# PIZ-Dual_v886.net
KiCad netlist of a schematic drawn in EAGLE
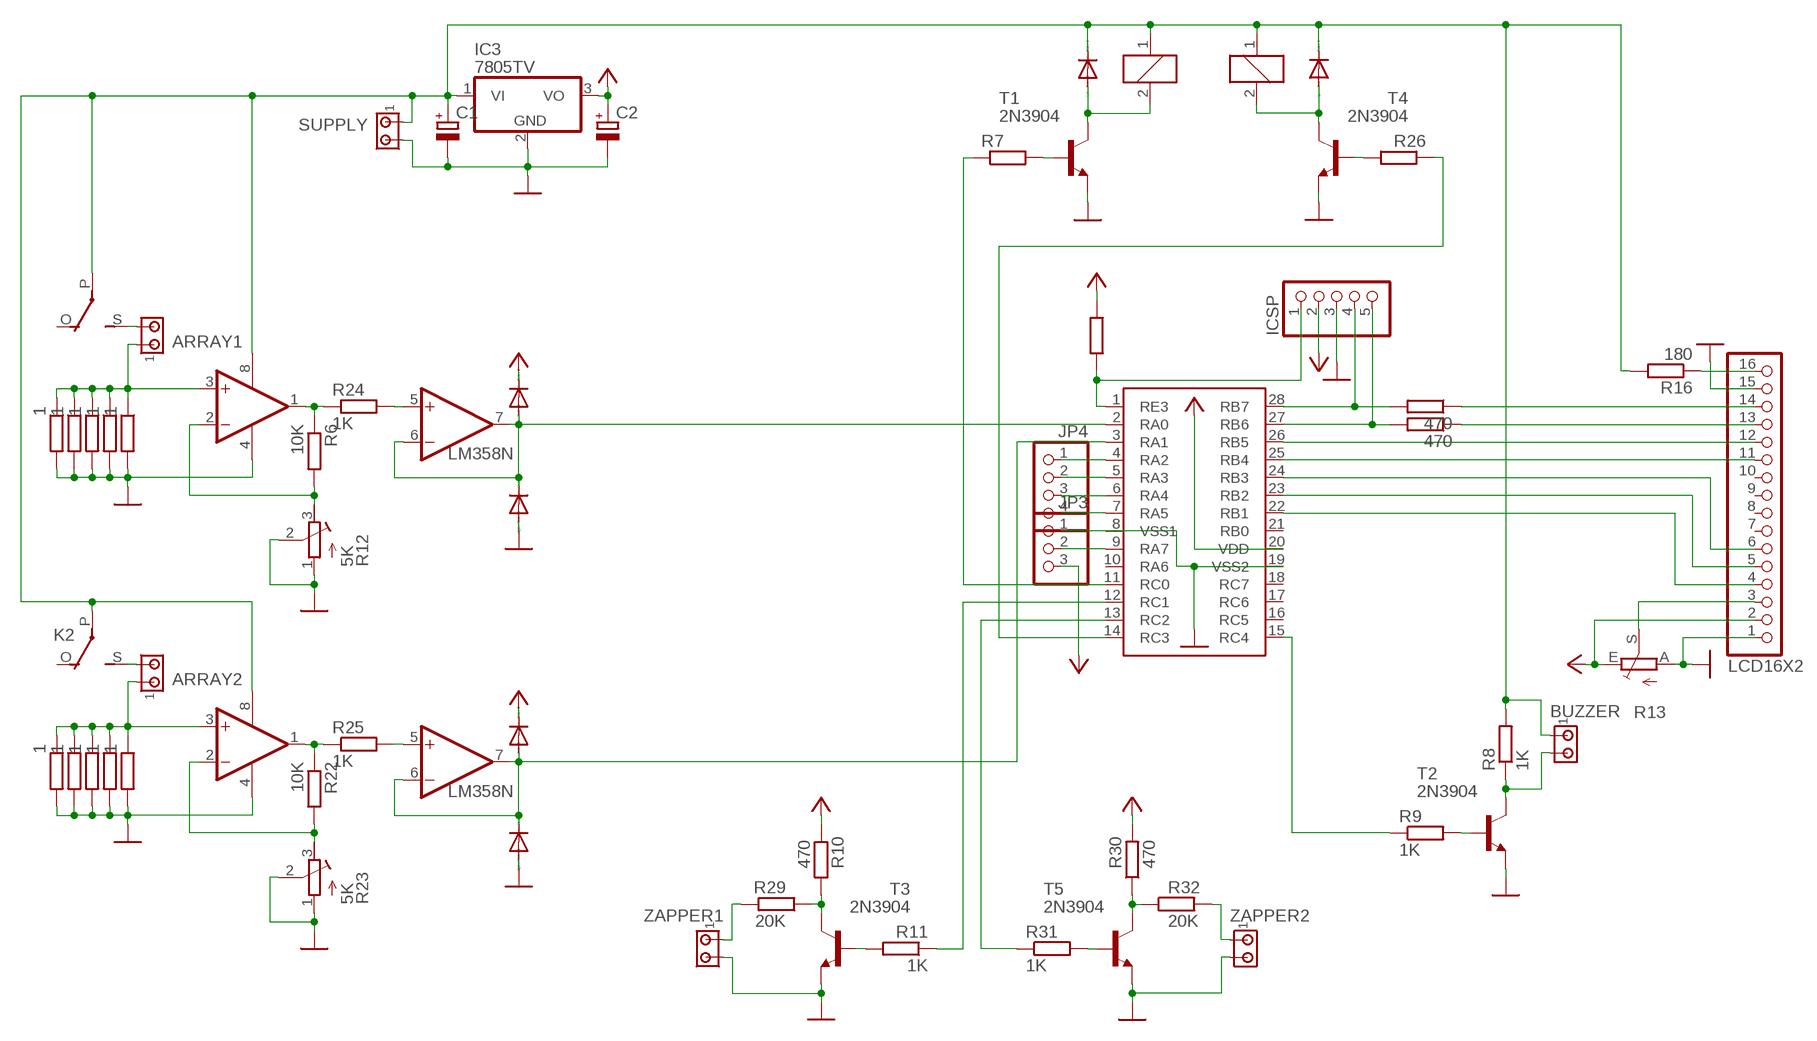
[diagram p0: schematic, sheet 1]

(export (version "E")
  (design (tool "Eeschema 10.0.6"))
  (components
    (comp (ref "ARRAY1")
      (value "MTA02-100")
      (footprint "eagle-import:10X02MTA")
      (libsource (lib "eagle-import") (part "MTA02-100"))
    )
    (comp (ref "ARRAY2")
      (value "MTA02-100")
      (footprint "eagle-import:10X02MTA")
      (libsource (lib "eagle-import") (part "MTA02-100"))
    )
    (comp (ref "BUZZER")
      (value "MTA02-100")
      (footprint "eagle-import:10X02MTA")
      (libsource (lib "eagle-import") (part "MTA02-100"))
    )
    (comp (ref "C1")
      (value "CPOL-EUE2.5-7")
      (footprint "eagle-import:E2,5-7")
      (libsource (lib "eagle-import") (part "CPOL-EUE2.5-7"))
    )
    (comp (ref "C2")
      (value "CPOL-EUE2.5-7")
      (footprint "eagle-import:E2,5-7")
      (libsource (lib "eagle-import") (part "CPOL-EUE2.5-7"))
    )
    (comp (ref "D1")
      (value "1N4148DO35-7")
      (footprint "eagle-import:DO35-7")
      (libsource (lib "eagle-import") (part "1N4148DO35-7"))
    )
    (comp (ref "D2")
      (value "1N4148DO35-7")
      (footprint "eagle-import:DO35-7")
      (libsource (lib "eagle-import") (part "1N4148DO35-7"))
    )
    (comp (ref "D3")
      (value "1N4148DO35-7")
      (footprint "eagle-import:DO35-7")
      (libsource (lib "eagle-import") (part "1N4148DO35-7"))
    )
    (comp (ref "D4")
      (value "1N4148DO35-7")
      (footprint "eagle-import:DO35-7")
      (libsource (lib "eagle-import") (part "1N4148DO35-7"))
    )
    (comp (ref "D5")
      (value "1N4148DO35-7")
      (footprint "eagle-import:DO35-7")
      (libsource (lib "eagle-import") (part "1N4148DO35-7"))
    )
    (comp (ref "D6")
      (value "1N4148DO35-7")
      (footprint "eagle-import:DO35-7")
      (libsource (lib "eagle-import") (part "1N4148DO35-7"))
    )
    (comp (ref "IC2")
      (value "LM358N")
      (footprint "eagle-import:DIL08")
      (libsource (lib "eagle-import") (part "LM358N"))
    )
    (comp (ref "IC3")
      (value "7805TV")
      (footprint "eagle-import:TO220V")
      (libsource (lib "eagle-import") (part "78TV05"))
    )
    (comp (ref "IC4")
      (value "LM358N")
      (footprint "eagle-import:DIL08")
      (libsource (lib "eagle-import") (part "LM358N"))
    )
    (comp (ref "ICSP")
      (value "PINHD-1X55X2MM")
      (footprint "eagle-import:1_05X2MM")
      (libsource (lib "eagle-import") (part "PINHD-1X55X2MM"))
    )
    (comp (ref "JP3")
      (value "PINHD-1X3")
      (footprint "eagle-import:1X03")
      (libsource (lib "eagle-import") (part "PINHD-1X3"))
    )
    (comp (ref "JP4")
      (value "PINHD-1X4")
      (footprint "eagle-import:1X04")
      (libsource (lib "eagle-import") (part "PINHD-1X4"))
    )
    (comp (ref "K1")
      (value "G5L")
      (footprint "eagle-import:G5LE")
      (libsource (lib "eagle-import") (part "G5L"))
    )
    (comp (ref "K2")
      (value "G5L")
      (footprint "eagle-import:G5LE")
      (libsource (lib "eagle-import") (part "G5L"))
    )
    (comp (ref "LCD16X2")
      (value "PINHD-1X16")
      (footprint "eagle-import:1X16")
      (libsource (lib "eagle-import") (part "PINHD-1X16"))
    )
    (comp (ref "R1")
      (value "1")
      (footprint "eagle-import:0204_7")
      (libsource (lib "eagle-import") (part "R-EU_0204/7"))
    )
    (comp (ref "R2")
      (value "1")
      (footprint "eagle-import:0204_7")
      (libsource (lib "eagle-import") (part "R-EU_0204/7"))
    )
    (comp (ref "R3")
      (value "1")
      (footprint "eagle-import:0204_7")
      (libsource (lib "eagle-import") (part "R-EU_0204/7"))
    )
    (comp (ref "R4")
      (value "1")
      (footprint "eagle-import:0204_7")
      (libsource (lib "eagle-import") (part "R-EU_0204/7"))
    )
    (comp (ref "R5")
      (value "1")
      (footprint "eagle-import:0204_7")
      (libsource (lib "eagle-import") (part "R-EU_0204/7"))
    )
    (comp (ref "R6")
      (value "10K")
      (footprint "eagle-import:0204_7")
      (libsource (lib "eagle-import") (part "R-EU_0204/7"))
    )
    (comp (ref "R7")
      (value "R-EU_0204/7")
      (footprint "eagle-import:0204_7")
      (libsource (lib "eagle-import") (part "R-EU_0204/7"))
    )
    (comp (ref "R8")
      (value "1K")
      (footprint "eagle-import:0204_7")
      (libsource (lib "eagle-import") (part "R-EU_0204/7"))
    )
    (comp (ref "R9")
      (value "1K")
      (footprint "eagle-import:0204_7")
      (libsource (lib "eagle-import") (part "R-EU_0204/7"))
    )
    (comp (ref "R10")
      (value "470")
      (footprint "eagle-import:0204_7")
      (libsource (lib "eagle-import") (part "R-EU_0204/7"))
    )
    (comp (ref "R11")
      (value "1K")
      (footprint "eagle-import:0204_7")
      (libsource (lib "eagle-import") (part "R-EU_0204/7"))
    )
    (comp (ref "R12")
      (value "5K")
      (footprint "eagle-import:RTRIM64W")
      (libsource (lib "eagle-import") (part "R-TRIMM64W"))
    )
    (comp (ref "R13")
      (value "TRIM_EU-CA6V")
      (footprint "eagle-import:CA6V")
      (libsource (lib "eagle-import") (part "TRIM_EU-CA6V"))
    )
    (comp (ref "R16")
      (value "180")
      (footprint "eagle-import:0309_10")
      (libsource (lib "eagle-import") (part "R-EU_0309/10"))
    )
    (comp (ref "R17")
      (value "1")
      (footprint "eagle-import:0204_7")
      (libsource (lib "eagle-import") (part "R-EU_0204/7"))
    )
    (comp (ref "R18")
      (value "1")
      (footprint "eagle-import:0204_7")
      (libsource (lib "eagle-import") (part "R-EU_0204/7"))
    )
    (comp (ref "R19")
      (value "1")
      (footprint "eagle-import:0204_7")
      (libsource (lib "eagle-import") (part "R-EU_0204/7"))
    )
    (comp (ref "R20")
      (value "1")
      (footprint "eagle-import:0204_7")
      (libsource (lib "eagle-import") (part "R-EU_0204/7"))
    )
    (comp (ref "R21")
      (value "1")
      (footprint "eagle-import:0204_7")
      (libsource (lib "eagle-import") (part "R-EU_0204/7"))
    )
    (comp (ref "R22")
      (value "10K")
      (footprint "eagle-import:0204_7")
      (libsource (lib "eagle-import") (part "R-EU_0204/7"))
    )
    (comp (ref "R23")
      (value "5K")
      (footprint "eagle-import:RTRIM64W")
      (libsource (lib "eagle-import") (part "R-TRIMM64W"))
    )
    (comp (ref "R24")
      (value "1K")
      (footprint "eagle-import:0204_7")
      (libsource (lib "eagle-import") (part "R-EU_0204/7"))
    )
    (comp (ref "R25")
      (value "1K")
      (footprint "eagle-import:0204_7")
      (libsource (lib "eagle-import") (part "R-EU_0204/7"))
    )
    (comp (ref "R26")
      (value "R-EU_0204/7")
      (footprint "eagle-import:0204_7")
      (libsource (lib "eagle-import") (part "R-EU_0204/7"))
    )
    (comp (ref "R27")
      (value "470")
      (footprint "eagle-import:0204_7")
      (libsource (lib "eagle-import") (part "R-EU_0204/7"))
    )
    (comp (ref "R28")
      (value "470")
      (footprint "eagle-import:0204_7")
      (libsource (lib "eagle-import") (part "R-EU_0204/7"))
    )
    (comp (ref "R29")
      (value "20K")
      (footprint "eagle-import:0204_7")
      (libsource (lib "eagle-import") (part "R-EU_0204/7"))
    )
    (comp (ref "R30")
      (value "470")
      (footprint "eagle-import:0204_7")
      (libsource (lib "eagle-import") (part "R-EU_0204/7"))
    )
    (comp (ref "R31")
      (value "1K")
      (footprint "eagle-import:0204_7")
      (libsource (lib "eagle-import") (part "R-EU_0204/7"))
    )
    (comp (ref "R32")
      (value "20K")
      (footprint "eagle-import:0204_7")
      (libsource (lib "eagle-import") (part "R-EU_0204/7"))
    )
    (comp (ref "R33")
      (value "10K")
      (footprint "eagle-import:0204_7")
      (libsource (lib "eagle-import") (part "R-EU_0204/7"))
    )
    (comp (ref "SUPPLY")
      (value "MTA02-100")
      (footprint "eagle-import:10X02MTA")
      (libsource (lib "eagle-import") (part "MTA02-100"))
    )
    (comp (ref "T1")
      (value "2N3904")
      (footprint "eagle-import:TO92")
      (libsource (lib "eagle-import") (part "2N3904"))
    )
    (comp (ref "T2")
      (value "2N3904")
      (footprint "eagle-import:TO92")
      (libsource (lib "eagle-import") (part "2N3904"))
    )
    (comp (ref "T3")
      (value "2N3904")
      (footprint "eagle-import:TO92")
      (libsource (lib "eagle-import") (part "2N3904"))
    )
    (comp (ref "T4")
      (value "2N3904")
      (footprint "eagle-import:TO92")
      (libsource (lib "eagle-import") (part "2N3904"))
    )
    (comp (ref "T5")
      (value "2N3904")
      (footprint "eagle-import:TO92")
      (libsource (lib "eagle-import") (part "2N3904"))
    )
    (comp (ref "U$1")
      (value "PIC16F88")
      (footprint "eagle-import:SO28W")
      (libsource (lib "eagle-import") (part "PIC16F88"))
    )
    (comp (ref "ZAPPER1")
      (value "MTA02-100")
      (footprint "eagle-import:10X02MTA")
      (libsource (lib "eagle-import") (part "MTA02-100"))
    )
    (comp (ref "ZAPPER2")
      (value "MTA02-100")
      (footprint "eagle-import:10X02MTA")
      (libsource (lib "eagle-import") (part "MTA02-100"))
    )
  )
  (nets
    (net (code "1") (name "GND") (class "Default")
      (node (ref "C1") (pin "-") (pinfunction "-_-") (pintype "passive"))
      (node (ref "C2") (pin "-") (pinfunction "-_-") (pintype "passive"))
      (node (ref "D2") (pin "A") (pinfunction "A_A") (pintype "passive"))
      (node (ref "D5") (pin "A") (pinfunction "A_A") (pintype "passive"))
      (node (ref "IC2") (pin "4") (pinfunction "V-_4") (pintype "power_in"))
      (node (ref "IC3") (pin "2") (pinfunction "GND_2") (pintype "passive"))
      (node (ref "IC4") (pin "4") (pinfunction "V-_4") (pintype "power_in"))
      (node (ref "ICSP") (pin "3") (pinfunction "3_3") (pintype "passive"))
      (node (ref "JP3") (pin "1") (pinfunction "1_1") (pintype "passive"))
      (node (ref "LCD16X2") (pin "1") (pinfunction "1_1") (pintype "passive"))
      (node (ref "LCD16X2") (pin "15") (pinfunction "15_15") (pintype "passive"))
      (node (ref "R1") (pin "2") (pinfunction "2_2") (pintype "passive"))
      (node (ref "R12") (pin "1") (pinfunction "A_1") (pintype "passive"))
      (node (ref "R12") (pin "2") (pinfunction "S_2") (pintype "passive"))
      (node (ref "R13") (pin "A") (pinfunction "A_A") (pintype "passive"))
      (node (ref "R17") (pin "2") (pinfunction "2_2") (pintype "passive"))
      (node (ref "R18") (pin "2") (pinfunction "2_2") (pintype "passive"))
      (node (ref "R19") (pin "2") (pinfunction "2_2") (pintype "passive"))
      (node (ref "R2") (pin "2") (pinfunction "2_2") (pintype "passive"))
      (node (ref "R20") (pin "2") (pinfunction "2_2") (pintype "passive"))
      (node (ref "R21") (pin "2") (pinfunction "2_2") (pintype "passive"))
      (node (ref "R23") (pin "1") (pinfunction "A_1") (pintype "passive"))
      (node (ref "R23") (pin "2") (pinfunction "S_2") (pintype "passive"))
      (node (ref "R3") (pin "2") (pinfunction "2_2") (pintype "passive"))
      (node (ref "R4") (pin "2") (pinfunction "2_2") (pintype "passive"))
      (node (ref "R5") (pin "2") (pinfunction "2_2") (pintype "passive"))
      (node (ref "SUPPLY") (pin "2") (pinfunction "2_2") (pintype "passive"))
      (node (ref "T1") (pin "3") (pinfunction "E_3") (pintype "passive"))
      (node (ref "T2") (pin "3") (pinfunction "E_3") (pintype "passive"))
      (node (ref "T3") (pin "3") (pinfunction "E_3") (pintype "passive"))
      (node (ref "T4") (pin "3") (pinfunction "E_3") (pintype "passive"))
      (node (ref "T5") (pin "3") (pinfunction "E_3") (pintype "passive"))
      (node (ref "U$1") (pin "19") (pinfunction "VSS2_19") (pintype "power_in"))
      (node (ref "U$1") (pin "8") (pinfunction "VSS1_8") (pintype "power_in"))
      (node (ref "ZAPPER1") (pin "2") (pinfunction "2_2") (pintype "passive"))
      (node (ref "ZAPPER2") (pin "2") (pinfunction "2_2") (pintype "passive"))
    )
    (net (code "2") (name "Net-(ARRAY1-Pad2)") (class "Default")
      (node (ref "ARRAY1") (pin "2") (pinfunction "2_2") (pintype "passive"))
      (node (ref "K1") (pin "S") (pinfunction "S_S") (pintype "passive"))
    )
    (net (code "3") (name "Net-(ARRAY2-Pad2)") (class "Default")
      (node (ref "ARRAY2") (pin "2") (pinfunction "2_2") (pintype "passive"))
      (node (ref "K2") (pin "S") (pinfunction "S_S") (pintype "passive"))
    )
    (net (code "4") (name "Net-(IC2A-+IN)") (class "Default")
      (node (ref "ARRAY1") (pin "1") (pinfunction "1_1") (pintype "passive"))
      (node (ref "IC2") (pin "3") (pinfunction "+IN_3") (pintype "input"))
      (node (ref "R1") (pin "1") (pinfunction "1_1") (pintype "passive"))
      (node (ref "R2") (pin "1") (pinfunction "1_1") (pintype "passive"))
      (node (ref "R3") (pin "1") (pinfunction "1_1") (pintype "passive"))
      (node (ref "R4") (pin "1") (pinfunction "1_1") (pintype "passive"))
      (node (ref "R5") (pin "1") (pinfunction "1_1") (pintype "passive"))
    )
    (net (code "5") (name "Net-(IC2A--IN)") (class "Default")
      (node (ref "IC2") (pin "2") (pinfunction "-IN_2") (pintype "input"))
      (node (ref "R12") (pin "3") (pinfunction "E_3") (pintype "passive"))
      (node (ref "R6") (pin "2") (pinfunction "2_2") (pintype "passive"))
    )
    (net (code "6") (name "Net-(IC2A-OUT)") (class "Default")
      (node (ref "IC2") (pin "1") (pinfunction "OUT_1") (pintype "output"))
      (node (ref "R24") (pin "1") (pinfunction "1_1") (pintype "passive"))
      (node (ref "R6") (pin "1") (pinfunction "1_1") (pintype "passive"))
    )
    (net (code "7") (name "Net-(IC2B-+IN)") (class "Default")
      (node (ref "IC2") (pin "5") (pinfunction "+IN_5") (pintype "input"))
      (node (ref "R24") (pin "2") (pinfunction "2_2") (pintype "passive"))
    )
    (net (code "8") (name "Net-(IC2B--IN)") (class "Default")
      (node (ref "D1") (pin "A") (pinfunction "A_A") (pintype "passive"))
      (node (ref "D2") (pin "C") (pinfunction "C_C") (pintype "passive"))
      (node (ref "IC2") (pin "6") (pinfunction "-IN_6") (pintype "input"))
      (node (ref "IC2") (pin "7") (pinfunction "OUT_7") (pintype "output"))
      (node (ref "U$1") (pin "2") (pinfunction "RA0_2") (pintype "bidirectional"))
    )
    (net (code "9") (name "Net-(IC2C-V+)") (class "Default")
      (node (ref "BUZZER") (pin "1") (pinfunction "1_1") (pintype "passive"))
      (node (ref "C1") (pin "+") (pinfunction "+_+") (pintype "passive"))
      (node (ref "D3") (pin "C") (pinfunction "C_C") (pintype "passive"))
      (node (ref "D6") (pin "C") (pinfunction "C_C") (pintype "passive"))
      (node (ref "IC2") (pin "8") (pinfunction "V+_8") (pintype "power_in"))
      (node (ref "IC3") (pin "1") (pinfunction "VI_1") (pintype "input"))
      (node (ref "IC4") (pin "8") (pinfunction "V+_8") (pintype "power_in"))
      (node (ref "K1") (pin "1") (pinfunction "1_1") (pintype "passive"))
      (node (ref "K1") (pin "P") (pinfunction "P_P") (pintype "passive"))
      (node (ref "K2") (pin "1") (pinfunction "1_1") (pintype "passive"))
      (node (ref "K2") (pin "P") (pinfunction "P_P") (pintype "passive"))
      (node (ref "R16") (pin "2") (pinfunction "2_2") (pintype "passive"))
      (node (ref "R8") (pin "2") (pinfunction "2_2") (pintype "passive"))
      (node (ref "SUPPLY") (pin "1") (pinfunction "1_1") (pintype "passive"))
    )
    (net (code "10") (name "Net-(IC4A-+IN)") (class "Default")
      (node (ref "ARRAY2") (pin "1") (pinfunction "1_1") (pintype "passive"))
      (node (ref "IC4") (pin "3") (pinfunction "+IN_3") (pintype "input"))
      (node (ref "R17") (pin "1") (pinfunction "1_1") (pintype "passive"))
      (node (ref "R18") (pin "1") (pinfunction "1_1") (pintype "passive"))
      (node (ref "R19") (pin "1") (pinfunction "1_1") (pintype "passive"))
      (node (ref "R20") (pin "1") (pinfunction "1_1") (pintype "passive"))
      (node (ref "R21") (pin "1") (pinfunction "1_1") (pintype "passive"))
    )
    (net (code "11") (name "Net-(IC4A--IN)") (class "Default")
      (node (ref "IC4") (pin "2") (pinfunction "-IN_2") (pintype "input"))
      (node (ref "R22") (pin "2") (pinfunction "2_2") (pintype "passive"))
      (node (ref "R23") (pin "3") (pinfunction "E_3") (pintype "passive"))
    )
    (net (code "12") (name "Net-(IC4A-OUT)") (class "Default")
      (node (ref "IC4") (pin "1") (pinfunction "OUT_1") (pintype "output"))
      (node (ref "R22") (pin "1") (pinfunction "1_1") (pintype "passive"))
      (node (ref "R25") (pin "1") (pinfunction "1_1") (pintype "passive"))
    )
    (net (code "13") (name "Net-(IC4B-+IN)") (class "Default")
      (node (ref "IC4") (pin "5") (pinfunction "+IN_5") (pintype "input"))
      (node (ref "R25") (pin "2") (pinfunction "2_2") (pintype "passive"))
    )
    (net (code "14") (name "Net-(IC4B--IN)") (class "Default")
      (node (ref "D4") (pin "A") (pinfunction "A_A") (pintype "passive"))
      (node (ref "D5") (pin "C") (pinfunction "C_C") (pintype "passive"))
      (node (ref "IC4") (pin "6") (pinfunction "-IN_6") (pintype "input"))
      (node (ref "IC4") (pin "7") (pinfunction "OUT_7") (pintype "output"))
      (node (ref "U$1") (pin "3") (pinfunction "RA1_3") (pintype "bidirectional"))
    )
    (net (code "15") (name "Net-(LCD16X2-Pad3)") (class "Default")
      (node (ref "LCD16X2") (pin "3") (pinfunction "3_3") (pintype "passive"))
      (node (ref "R13") (pin "S") (pinfunction "S_S") (pintype "passive"))
    )
    (net (code "16") (name "Net-(LCD16X2-Pad13)") (class "Default")
      (node (ref "LCD16X2") (pin "13") (pinfunction "13_13") (pintype "passive"))
      (node (ref "R28") (pin "1") (pinfunction "1_1") (pintype "passive"))
    )
    (net (code "17") (name "Net-(LCD16X2-Pad14)") (class "Default")
      (node (ref "LCD16X2") (pin "14") (pinfunction "14_14") (pintype "passive"))
      (node (ref "R27") (pin "1") (pinfunction "1_1") (pintype "passive"))
    )
    (net (code "18") (name "Net-(LCD16X2-Pad16)") (class "Default")
      (node (ref "LCD16X2") (pin "16") (pinfunction "16_16") (pintype "passive"))
      (node (ref "R16") (pin "1") (pinfunction "1_1") (pintype "passive"))
    )
    (net (code "19") (name "Net-(R29-Pad2)") (class "Default")
      (node (ref "R29") (pin "2") (pinfunction "2_2") (pintype "passive"))
      (node (ref "ZAPPER1") (pin "1") (pinfunction "1_1") (pintype "passive"))
    )
    (net (code "20") (name "Net-(R32-Pad2)") (class "Default")
      (node (ref "R32") (pin "2") (pinfunction "2_2") (pintype "passive"))
      (node (ref "ZAPPER2") (pin "1") (pinfunction "1_1") (pintype "passive"))
    )
    (net (code "21") (name "Net-(T1-B)") (class "Default")
      (node (ref "R7") (pin "2") (pinfunction "2_2") (pintype "passive"))
      (node (ref "T1") (pin "2") (pinfunction "B_2") (pintype "passive"))
    )
    (net (code "22") (name "Net-(T1-C)") (class "Default")
      (node (ref "D3") (pin "A") (pinfunction "A_A") (pintype "passive"))
      (node (ref "K1") (pin "2") (pinfunction "2_2") (pintype "passive"))
      (node (ref "T1") (pin "1") (pinfunction "C_1") (pintype "passive"))
    )
    (net (code "23") (name "Net-(T2-B)") (class "Default")
      (node (ref "R9") (pin "2") (pinfunction "2_2") (pintype "passive"))
      (node (ref "T2") (pin "2") (pinfunction "B_2") (pintype "passive"))
    )
    (net (code "24") (name "Net-(T2-C)") (class "Default")
      (node (ref "BUZZER") (pin "2") (pinfunction "2_2") (pintype "passive"))
      (node (ref "R8") (pin "1") (pinfunction "1_1") (pintype "passive"))
      (node (ref "T2") (pin "1") (pinfunction "C_1") (pintype "passive"))
    )
    (net (code "25") (name "Net-(T3-B)") (class "Default")
      (node (ref "R11") (pin "2") (pinfunction "2_2") (pintype "passive"))
      (node (ref "T3") (pin "2") (pinfunction "B_2") (pintype "passive"))
    )
    (net (code "26") (name "Net-(T3-C)") (class "Default")
      (node (ref "R10") (pin "1") (pinfunction "1_1") (pintype "passive"))
      (node (ref "R29") (pin "1") (pinfunction "1_1") (pintype "passive"))
      (node (ref "T3") (pin "1") (pinfunction "C_1") (pintype "passive"))
    )
    (net (code "27") (name "Net-(T4-B)") (class "Default")
      (node (ref "R26") (pin "2") (pinfunction "2_2") (pintype "passive"))
      (node (ref "T4") (pin "2") (pinfunction "B_2") (pintype "passive"))
    )
    (net (code "28") (name "Net-(T4-C)") (class "Default")
      (node (ref "D6") (pin "A") (pinfunction "A_A") (pintype "passive"))
      (node (ref "K2") (pin "2") (pinfunction "2_2") (pintype "passive"))
      (node (ref "T4") (pin "1") (pinfunction "C_1") (pintype "passive"))
    )
    (net (code "29") (name "Net-(T5-B)") (class "Default")
      (node (ref "R31") (pin "2") (pinfunction "2_2") (pintype "passive"))
      (node (ref "T5") (pin "2") (pinfunction "B_2") (pintype "passive"))
    )
    (net (code "30") (name "Net-(T5-C)") (class "Default")
      (node (ref "R30") (pin "1") (pinfunction "1_1") (pintype "passive"))
      (node (ref "R32") (pin "1") (pinfunction "1_1") (pintype "passive"))
      (node (ref "T5") (pin "1") (pinfunction "C_1") (pintype "passive"))
    )
    (net (code "31") (name "Net-(U$1-RA2)") (class "Default")
      (node (ref "JP4") (pin "1") (pinfunction "1_1") (pintype "passive"))
      (node (ref "U$1") (pin "4") (pinfunction "RA2_4") (pintype "bidirectional"))
    )
    (net (code "32") (name "Net-(U$1-RA3)") (class "Default")
      (node (ref "JP4") (pin "2") (pinfunction "2_2") (pintype "passive"))
      (node (ref "U$1") (pin "5") (pinfunction "RA3_5") (pintype "bidirectional"))
    )
    (net (code "33") (name "Net-(U$1-RA4)") (class "Default")
      (node (ref "JP4") (pin "3") (pinfunction "3_3") (pintype "passive"))
      (node (ref "U$1") (pin "6") (pinfunction "RA4_6") (pintype "bidirectional"))
    )
    (net (code "34") (name "Net-(U$1-RA5)") (class "Default")
      (node (ref "JP4") (pin "4") (pinfunction "4_4") (pintype "passive"))
      (node (ref "U$1") (pin "7") (pinfunction "RA5_7") (pintype "bidirectional"))
    )
    (net (code "35") (name "Net-(U$1-RA7)") (class "Default")
      (node (ref "JP3") (pin "2") (pinfunction "2_2") (pintype "passive"))
      (node (ref "U$1") (pin "9") (pinfunction "RA7_9") (pintype "bidirectional"))
    )
    (net (code "36") (name "Net-(U$1-RB1)") (class "Default")
      (node (ref "LCD16X2") (pin "4") (pinfunction "4_4") (pintype "passive"))
      (node (ref "U$1") (pin "22") (pinfunction "RB1_22") (pintype "bidirectional"))
    )
    (net (code "37") (name "Net-(U$1-RB2)") (class "Default")
      (node (ref "LCD16X2") (pin "5") (pinfunction "5_5") (pintype "passive"))
      (node (ref "U$1") (pin "23") (pinfunction "RB2_23") (pintype "bidirectional"))
    )
    (net (code "38") (name "Net-(U$1-RB3)") (class "Default")
      (node (ref "LCD16X2") (pin "6") (pinfunction "6_6") (pintype "passive"))
      (node (ref "U$1") (pin "24") (pinfunction "RB3_24") (pintype "bidirectional"))
    )
    (net (code "39") (name "Net-(U$1-RB4)") (class "Default")
      (node (ref "LCD16X2") (pin "11") (pinfunction "11_11") (pintype "passive"))
      (node (ref "U$1") (pin "25") (pinfunction "RB4_25") (pintype "bidirectional"))
    )
    (net (code "40") (name "Net-(U$1-RB5)") (class "Default")
      (node (ref "LCD16X2") (pin "12") (pinfunction "12_12") (pintype "passive"))
      (node (ref "U$1") (pin "26") (pinfunction "RB5_26") (pintype "bidirectional"))
    )
    (net (code "41") (name "Net-(U$1-RB6)") (class "Default")
      (node (ref "ICSP") (pin "5") (pinfunction "5_5") (pintype "passive"))
      (node (ref "R28") (pin "2") (pinfunction "2_2") (pintype "passive"))
      (node (ref "U$1") (pin "27") (pinfunction "RB6_27") (pintype "bidirectional"))
    )
    (net (code "42") (name "Net-(U$1-RB7)") (class "Default")
      (node (ref "ICSP") (pin "4") (pinfunction "4_4") (pintype "passive"))
      (node (ref "R27") (pin "2") (pinfunction "2_2") (pintype "passive"))
      (node (ref "U$1") (pin "28") (pinfunction "RB7_28") (pintype "bidirectional"))
    )
    (net (code "43") (name "Net-(U$1-RC0)") (class "Default")
      (node (ref "R7") (pin "1") (pinfunction "1_1") (pintype "passive"))
      (node (ref "U$1") (pin "11") (pinfunction "RC0_11") (pintype "bidirectional"))
    )
    (net (code "44") (name "Net-(U$1-RC1)") (class "Default")
      (node (ref "R11") (pin "1") (pinfunction "1_1") (pintype "passive"))
      (node (ref "U$1") (pin "12") (pinfunction "RC1_12") (pintype "bidirectional"))
    )
    (net (code "45") (name "Net-(U$1-RC2)") (class "Default")
      (node (ref "R31") (pin "1") (pinfunction "1_1") (pintype "passive"))
      (node (ref "U$1") (pin "13") (pinfunction "RC2_13") (pintype "bidirectional"))
    )
    (net (code "46") (name "Net-(U$1-RC3)") (class "Default")
      (node (ref "R26") (pin "1") (pinfunction "1_1") (pintype "passive"))
      (node (ref "U$1") (pin "14") (pinfunction "RC3_14") (pintype "bidirectional"))
    )
    (net (code "47") (name "Net-(U$1-RC4)") (class "Default")
      (node (ref "R9") (pin "1") (pinfunction "1_1") (pintype "passive"))
      (node (ref "U$1") (pin "15") (pinfunction "RC4_15") (pintype "bidirectional"))
    )
    (net (code "48") (name "Net-(U$1-RE3)") (class "Default")
      (node (ref "ICSP") (pin "1") (pinfunction "1_1") (pintype "passive"))
      (node (ref "R33") (pin "2") (pinfunction "2_2") (pintype "passive"))
      (node (ref "U$1") (pin "1") (pinfunction "RE3_1") (pintype "bidirectional"))
    )
    (net (code "49") (name "VCC") (class "Default")
      (node (ref "C2") (pin "+") (pinfunction "+_+") (pintype "passive"))
      (node (ref "D1") (pin "C") (pinfunction "C_C") (pintype "passive"))
      (node (ref "D4") (pin "C") (pinfunction "C_C") (pintype "passive"))
      (node (ref "IC3") (pin "3") (pinfunction "VO_3") (pintype "passive"))
      (node (ref "ICSP") (pin "2") (pinfunction "2_2") (pintype "passive"))
      (node (ref "JP3") (pin "3") (pinfunction "3_3") (pintype "passive"))
      (node (ref "LCD16X2") (pin "2") (pinfunction "2_2") (pintype "passive"))
      (node (ref "R10") (pin "2") (pinfunction "2_2") (pintype "passive"))
      (node (ref "R13") (pin "E") (pinfunction "E_E") (pintype "passive"))
      (node (ref "R30") (pin "2") (pinfunction "2_2") (pintype "passive"))
      (node (ref "R33") (pin "1") (pinfunction "1_1") (pintype "passive"))
      (node (ref "U$1") (pin "20") (pinfunction "VDD_20") (pintype "power_in"))
    )
    (net (code "50") (name "unconnected-(K1-PadO)") (class "Default")
      (node (ref "K1") (pin "O") (pinfunction "O_O") (pintype "passive"))
    )
    (net (code "51") (name "unconnected-(K2-PadO)") (class "Default")
      (node (ref "K2") (pin "O") (pinfunction "O_O") (pintype "passive"))
    )
    (net (code "52") (name "unconnected-(LCD16X2-Pad7)") (class "Default")
      (node (ref "LCD16X2") (pin "7") (pinfunction "7_7") (pintype "passive"))
    )
    (net (code "53") (name "unconnected-(LCD16X2-Pad8)") (class "Default")
      (node (ref "LCD16X2") (pin "8") (pinfunction "8_8") (pintype "passive"))
    )
    (net (code "54") (name "unconnected-(LCD16X2-Pad9)") (class "Default")
      (node (ref "LCD16X2") (pin "9") (pinfunction "9_9") (pintype "passive"))
    )
    (net (code "55") (name "unconnected-(LCD16X2-Pad10)") (class "Default")
      (node (ref "LCD16X2") (pin "10") (pinfunction "10_10") (pintype "passive"))
    )
    (net (code "56") (name "unconnected-(U$1-RA6-Pad10)") (class "Default")
      (node (ref "U$1") (pin "10") (pinfunction "RA6_10") (pintype "bidirectional"))
    )
    (net (code "57") (name "unconnected-(U$1-RB0-Pad21)") (class "Default")
      (node (ref "U$1") (pin "21") (pinfunction "RB0_21") (pintype "bidirectional"))
    )
    (net (code "58") (name "unconnected-(U$1-RC5-Pad16)") (class "Default")
      (node (ref "U$1") (pin "16") (pinfunction "RC5_16") (pintype "bidirectional"))
    )
    (net (code "59") (name "unconnected-(U$1-RC6-Pad17)") (class "Default")
      (node (ref "U$1") (pin "17") (pinfunction "RC6_17") (pintype "bidirectional"))
    )
    (net (code "60") (name "unconnected-(U$1-RC7-Pad18)") (class "Default")
      (node (ref "U$1") (pin "18") (pinfunction "RC7_18") (pintype "bidirectional"))
    )
  )
)
